# luminet_adapter.net
KiCad netlist of a schematic drawn in EAGLE
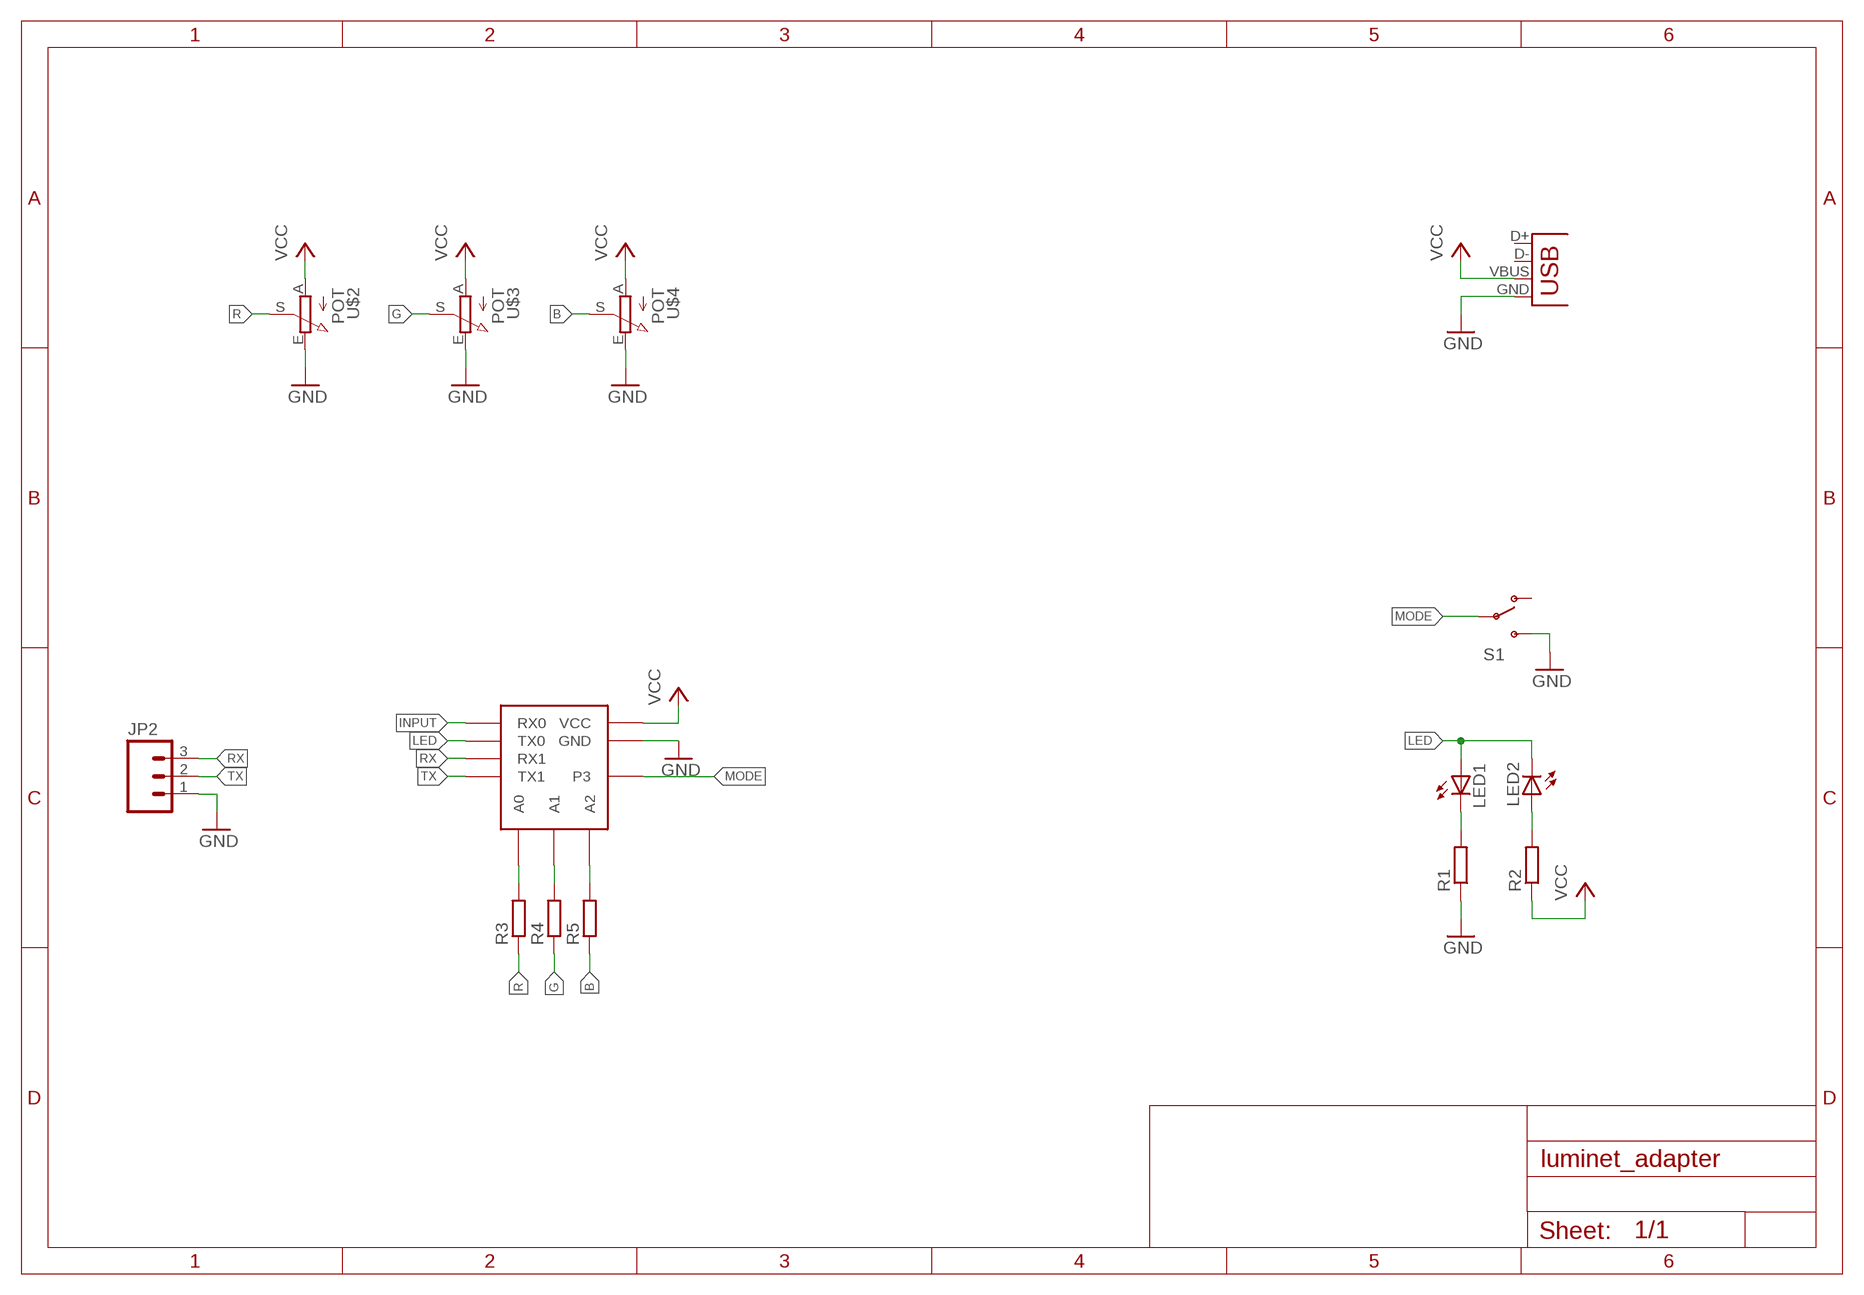
[diagram p0: schematic, sheet 1]

(export (version "E")
  (design (tool "Eeschema 10.0.6"))
  (components
    (comp (ref "JP1")
      (value "USBOLD")
      (footprint "eagle-import:USB-MINIB-OLD")
      (libsource (lib "eagle-import") (part "USBOLD"))
    )
    (comp (ref "JP2")
      (value "M03LOCK_LONGPADS")
      (footprint "eagle-import:1X03_LOCK_LONGPADS")
      (libsource (lib "eagle-import") (part "M03LOCK_LONGPADS"))
    )
    (comp (ref "LED1")
      (value "LEDCHIPLED_1206")
      (footprint "eagle-import:CHIPLED_1206")
      (libsource (lib "eagle-import") (part "LEDCHIPLED_1206"))
    )
    (comp (ref "LED2")
      (value "LEDCHIPLED_1206")
      (footprint "eagle-import:CHIPLED_1206")
      (libsource (lib "eagle-import") (part "LEDCHIPLED_1206"))
    )
    (comp (ref "R1")
      (value "R-EU_R0805")
      (footprint "eagle-import:R0805")
      (libsource (lib "eagle-import") (part "R-EU_R0805"))
    )
    (comp (ref "R2")
      (value "R-EU_R0805")
      (footprint "eagle-import:R0805")
      (libsource (lib "eagle-import") (part "R-EU_R0805"))
    )
    (comp (ref "R3")
      (value "R-EU_R0805")
      (footprint "eagle-import:R0805")
      (libsource (lib "eagle-import") (part "R-EU_R0805"))
    )
    (comp (ref "R4")
      (value "R-EU_R0805")
      (footprint "eagle-import:R0805")
      (libsource (lib "eagle-import") (part "R-EU_R0805"))
    )
    (comp (ref "R5")
      (value "R-EU_R0805")
      (footprint "eagle-import:R0805")
      (libsource (lib "eagle-import") (part "R-EU_R0805"))
    )
    (comp (ref "S1")
      (value "SWITCH-SPDT-SMD-A")
      (footprint "eagle-import:SWITCH-SPST-SMD-A")
      (libsource (lib "eagle-import") (part "SWITCH-SPDT-SMD-A"))
    )
    (comp (ref "U$1")
      (value "LUMINET2")
      (footprint "eagle-import:LUMINET_ADAPTER")
      (libsource (lib "eagle-import") (part "LUMINET2"))
    )
    (comp (ref "U$2")
      (value "POT")
      (footprint "eagle-import:POTENTIOMETER")
      (libsource (lib "eagle-import") (part "POT"))
    )
    (comp (ref "U$3")
      (value "POT")
      (footprint "eagle-import:POTENTIOMETER")
      (libsource (lib "eagle-import") (part "POT"))
    )
    (comp (ref "U$4")
      (value "POT")
      (footprint "eagle-import:POTENTIOMETER")
      (libsource (lib "eagle-import") (part "POT"))
    )
  )
  (nets
    (net (code "1") (name "B") (class "Default")
      (node (ref "R5") (pin "1") (pinfunction "1_1") (pintype "passive"))
      (node (ref "U$4") (pin "S") (pinfunction "S_S") (pintype "passive"))
    )
    (net (code "2") (name "G") (class "Default")
      (node (ref "R4") (pin "1") (pinfunction "1_1") (pintype "passive"))
      (node (ref "U$3") (pin "S") (pinfunction "S_S") (pintype "passive"))
    )
    (net (code "3") (name "GND") (class "Default")
      (node (ref "JP1") (pin "GND") (pinfunction "GND_GND") (pintype "bidirectional"))
      (node (ref "JP2") (pin "1") (pinfunction "1_1") (pintype "passive"))
      (node (ref "R1") (pin "1") (pinfunction "1_1") (pintype "passive"))
      (node (ref "S1") (pin "3") (pinfunction "S_3") (pintype "passive"))
      (node (ref "U$1") (pin "GND@1") (pinfunction "GND_GND@1") (pintype "bidirectional"))
      (node (ref "U$1") (pin "GND@2") (pinfunction "GND_GND@2") (pintype "bidirectional"))
      (node (ref "U$1") (pin "GND@3") (pinfunction "GND_GND@3") (pintype "bidirectional"))
      (node (ref "U$2") (pin "E") (pinfunction "E_E") (pintype "passive"))
      (node (ref "U$3") (pin "E") (pinfunction "E_E") (pintype "passive"))
      (node (ref "U$4") (pin "E") (pinfunction "E_E") (pintype "passive"))
    )
    (net (code "4") (name "INPUT") (class "Default")
      (node (ref "U$1") (pin "RX0") (pinfunction "RX0_RX0") (pintype "bidirectional"))
    )
    (net (code "5") (name "LED") (class "Default")
      (node (ref "LED1") (pin "A") (pinfunction "A_A") (pintype "passive"))
      (node (ref "LED2") (pin "C") (pinfunction "C_C") (pintype "passive"))
      (node (ref "U$1") (pin "TX0") (pinfunction "TX0_TX0") (pintype "bidirectional"))
    )
    (net (code "6") (name "MODE") (class "Default")
      (node (ref "S1") (pin "2") (pinfunction "P_2") (pintype "passive"))
      (node (ref "U$1") (pin "P3") (pinfunction "P3_P3") (pintype "bidirectional"))
    )
    (net (code "7") (name "Net-(LED1-PadC)") (class "Default")
      (node (ref "LED1") (pin "C") (pinfunction "C_C") (pintype "passive"))
      (node (ref "R1") (pin "2") (pinfunction "2_2") (pintype "passive"))
    )
    (net (code "8") (name "Net-(LED2-PadA)") (class "Default")
      (node (ref "LED2") (pin "A") (pinfunction "A_A") (pintype "passive"))
      (node (ref "R2") (pin "2") (pinfunction "2_2") (pintype "passive"))
    )
    (net (code "9") (name "Net-(R3-Pad2)") (class "Default")
      (node (ref "R3") (pin "2") (pinfunction "2_2") (pintype "passive"))
      (node (ref "U$1") (pin "A0") (pinfunction "A0_A0") (pintype "bidirectional"))
    )
    (net (code "10") (name "Net-(R4-Pad2)") (class "Default")
      (node (ref "R4") (pin "2") (pinfunction "2_2") (pintype "passive"))
      (node (ref "U$1") (pin "A1") (pinfunction "A1_A1") (pintype "bidirectional"))
    )
    (net (code "11") (name "Net-(R5-Pad2)") (class "Default")
      (node (ref "R5") (pin "2") (pinfunction "2_2") (pintype "passive"))
      (node (ref "U$1") (pin "A2") (pinfunction "A2_A2") (pintype "bidirectional"))
    )
    (net (code "12") (name "R") (class "Default")
      (node (ref "R3") (pin "1") (pinfunction "1_1") (pintype "passive"))
      (node (ref "U$2") (pin "S") (pinfunction "S_S") (pintype "passive"))
    )
    (net (code "13") (name "RX") (class "Default")
      (node (ref "JP2") (pin "3") (pinfunction "3_3") (pintype "passive"))
      (node (ref "U$1") (pin "RX1") (pinfunction "RX1_RX1") (pintype "bidirectional"))
    )
    (net (code "14") (name "TX") (class "Default")
      (node (ref "JP2") (pin "2") (pinfunction "2_2") (pintype "passive"))
      (node (ref "U$1") (pin "TX1") (pinfunction "TX1_TX1") (pintype "bidirectional"))
    )
    (net (code "15") (name "VCC") (class "Default")
      (node (ref "JP1") (pin "VBUS") (pinfunction "VBUS_VBUS") (pintype "bidirectional"))
      (node (ref "R2") (pin "1") (pinfunction "1_1") (pintype "passive"))
      (node (ref "U$1") (pin "VCC@1") (pinfunction "VCC_VCC@1") (pintype "bidirectional"))
      (node (ref "U$1") (pin "VCC@2") (pinfunction "VCC_VCC@2") (pintype "bidirectional"))
      (node (ref "U$1") (pin "VCC@3") (pinfunction "VCC_VCC@3") (pintype "bidirectional"))
      (node (ref "U$2") (pin "A") (pinfunction "A_A") (pintype "passive"))
      (node (ref "U$3") (pin "A") (pinfunction "A_A") (pintype "passive"))
      (node (ref "U$4") (pin "A") (pinfunction "A_A") (pintype "passive"))
    )
    (net (code "16") (name "unconnected-(JP1-PadD+)") (class "Default")
      (node (ref "JP1") (pin "D+") (pinfunction "D+_D+") (pintype "bidirectional"))
    )
    (net (code "17") (name "unconnected-(JP1-PadD-)") (class "Default")
      (node (ref "JP1") (pin "D-") (pinfunction "D-_D-") (pintype "bidirectional"))
    )
    (net (code "18") (name "unconnected-(S1-O-Pad1)") (class "Default")
      (node (ref "S1") (pin "1") (pinfunction "O_1") (pintype "passive"))
    )
  )
)
